# Ctrol_DC.net
KiCad netlist of a schematic drawn in Altium Designer
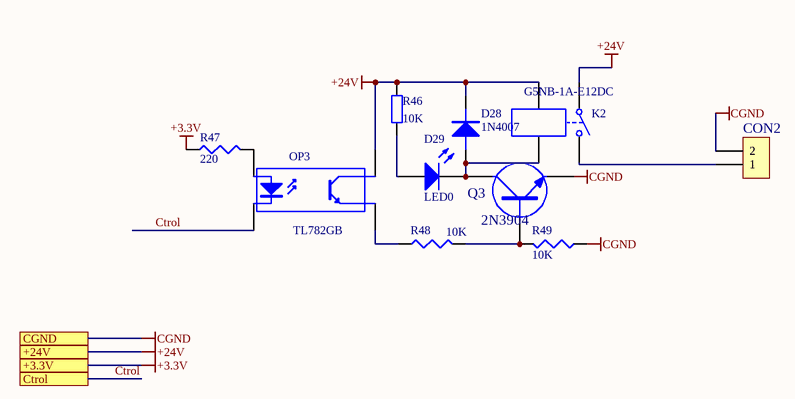
[diagram p0: Ctrol_DC.SchDoc]

(export (version "E")
  (design (tool "Eeschema 10.0.6"))
  (components
    (comp (ref "CON2")
      (value "~")
      (footprint "DG142V-5.08-2P")
      (description "Connector")
      (libsource (lib "*") (part "CON2"))
    )
    (comp (ref "D28")
      (value "1N4007")
      (footprint "DO-213AB")
      (description "Diode")
      (libsource (lib "*") (part "DIODE"))
    )
    (comp (ref "D29")
      (value "LED0")
      (footprint "D0805")
      (description "Typical INFRARED GaAs LED")
      (fields (field (name "PUBLISHER") "Altium Limited"))
      (libsource (lib "Miscellaneous Devices") (part "LED0"))
    )
    (comp (ref "K2")
      (value "G5NB-1A-E12DC")
      (footprint "G5NB-1A-E")
      (description "Single-Pole Single-Throw Relay")
      (fields (field (name "PUBLISHER") "Altium Limited"))
      (libsource (lib "main board fo stk") (part "Relay-G5NB-1A-E"))
    )
    (comp (ref "OP3")
      (value "TL782GB")
      (footprint "TLV-356")
      (description "Optoisolator")
      (libsource (lib "*") (part "OPTOISO1"))
    )
    (comp (ref "Q3") (value "2N3904") (footprint "SOT-23") (libsource (lib "*") (part "8050")))
    (comp (ref "R46")
      (value "10K")
      (footprint "0603R")
      (description "Resistor")
      (fields (field (name "PUBLISHER") "Altium Limited"))
      (libsource (lib "Miscellaneous Devices") (part "Res2"))
    )
    (comp (ref "R47") (value "220") (footprint "0603R") (libsource (lib "*") (part "RES1")))
    (comp (ref "R48") (value "10K") (footprint "0603R") (libsource (lib "*") (part "RES1")))
    (comp (ref "R49") (value "10K") (footprint "0603R") (libsource (lib "*") (part "RES1")))
  )
  (nets
    (net (code "1") (name "+3.3V") (class "Default")
      (node (ref "R47") (pin "1") (pinfunction "1_1") (pintype "passive"))
    )
    (net (code "2") (name "+24V") (class "Default")
      (node (ref "D28") (pin "2") (pinfunction "K_2") (pintype "passive"))
      (node (ref "K2") (pin "1") (pinfunction "1_1") (pintype "passive"))
      (node (ref "K2") (pin "2") (pinfunction "2_2") (pintype "passive"))
      (node (ref "OP3") (pin "4") (pinfunction "C_4") (pintype "passive"))
      (node (ref "R46") (pin "1") (pinfunction "1_1") (pintype "passive"))
    )
    (net (code "3") (name "/Ctrol") (class "Default")
      (node (ref "OP3") (pin "2") (pinfunction "K_2") (pintype "passive"))
    )
    (net (code "4") (name "CGND") (class "Default")
      (node (ref "CON2") (pin "2") (pinfunction "2_2") (pintype "passive"))
      (node (ref "Q3") (pin "2") (pinfunction "E_2") (pintype "passive"))
      (node (ref "R49") (pin "1") (pinfunction "1_1") (pintype "passive"))
    )
    (net (code "5") (name "Net-(CON2-Pad1)") (class "Default")
      (node (ref "CON2") (pin "1") (pinfunction "1_1") (pintype "passive"))
      (node (ref "K2") (pin "3") (pinfunction "3_3") (pintype "passive"))
    )
    (net (code "6") (name "Net-(D28-A)") (class "Default")
      (node (ref "D28") (pin "1") (pinfunction "A_1") (pintype "passive"))
      (node (ref "D29") (pin "2") (pinfunction "K_2") (pintype "passive"))
      (node (ref "K2") (pin "4") (pinfunction "4_4") (pintype "passive"))
      (node (ref "Q3") (pin "3") (pinfunction "C_3") (pintype "passive"))
    )
    (net (code "7") (name "Net-(D29-A)") (class "Default")
      (node (ref "D29") (pin "1") (pinfunction "A_1") (pintype "passive"))
      (node (ref "R46") (pin "2") (pinfunction "2_2") (pintype "passive"))
    )
    (net (code "8") (name "Net-(OP3-A)") (class "Default")
      (node (ref "OP3") (pin "1") (pinfunction "A_1") (pintype "passive"))
      (node (ref "R47") (pin "2") (pinfunction "2_2") (pintype "passive"))
    )
    (net (code "9") (name "Net-(OP3-E)") (class "Default")
      (node (ref "OP3") (pin "3") (pinfunction "E_3") (pintype "passive"))
      (node (ref "R48") (pin "1") (pinfunction "1_1") (pintype "passive"))
    )
    (net (code "10") (name "Net-(Q3-B)") (class "Default")
      (node (ref "Q3") (pin "1") (pinfunction "B_1") (pintype "passive"))
      (node (ref "R48") (pin "2") (pinfunction "2_2") (pintype "passive"))
      (node (ref "R49") (pin "2") (pinfunction "2_2") (pintype "passive"))
    )
  )
)
